# FlightControl.net
KiCad netlist of a schematic drawn in EAGLE
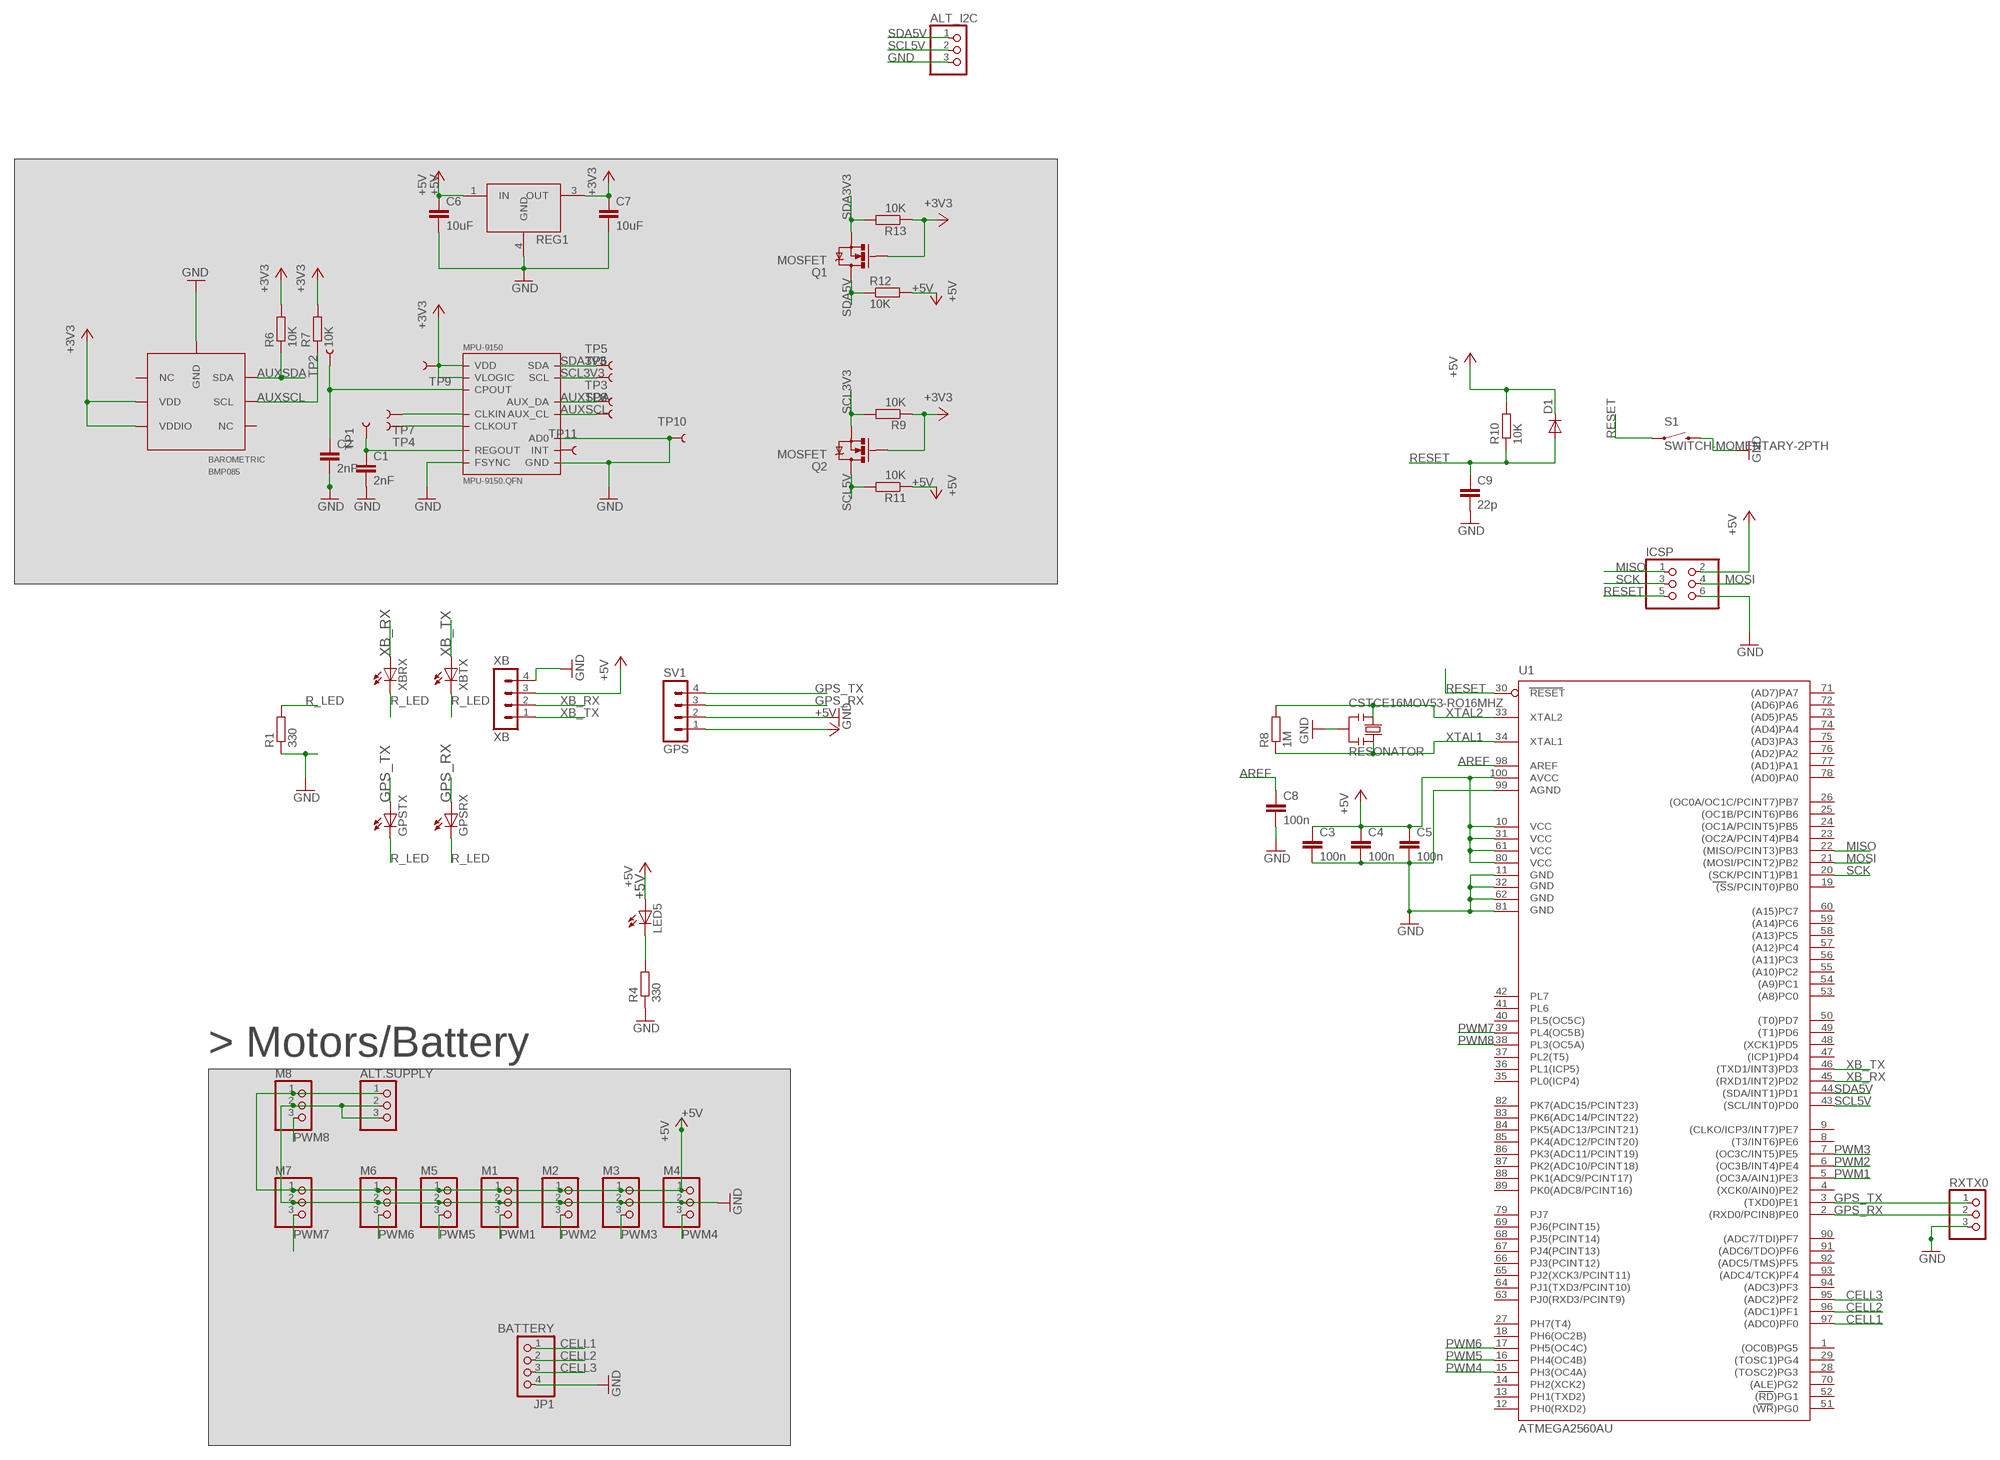
[diagram p0: schematic, sheet 1]

(export (version "E")
  (design (tool "Eeschema 10.0.6"))
  (components
    (comp (ref "ALT.SUPPLY")
      (value "PINHD-1X3")
      (footprint "eagle-import:1X03")
      (libsource (lib "eagle-import") (part "PINHD-1X3"))
    )
    (comp (ref "ALT_I2C")
      (value "PINHD-1X3")
      (footprint "eagle-import:1X03")
      (libsource (lib "eagle-import") (part "PINHD-1X3"))
    )
    (comp (ref "BAROMETRIC")
      (value "BMP085")
      (footprint "eagle-import:7LGA")
      (libsource (lib "eagle-import") (part "BMP085"))
    )
    (comp (ref "BATTERY")
      (value "JP1")
      (footprint "eagle-import:1X04")
      (libsource (lib "eagle-import") (part "PINHD-1X4"))
    )
    (comp (ref "C1")
      (value "2nF")
      (footprint "eagle-import:C0603-ROUND")
      (libsource (lib "eagle-import") (part "C-EUC0603"))
    )
    (comp (ref "C2")
      (value "2nF")
      (footprint "eagle-import:C0603-ROUND")
      (libsource (lib "eagle-import") (part "C-EUC0603"))
    )
    (comp (ref "C3")
      (value "100n")
      (footprint "eagle-import:C0603-ROUND")
      (libsource (lib "eagle-import") (part "C-EU0603-RND"))
    )
    (comp (ref "C4")
      (value "100n")
      (footprint "eagle-import:C0603-ROUND")
      (libsource (lib "eagle-import") (part "C-EU0603-RND"))
    )
    (comp (ref "C5")
      (value "100n")
      (footprint "eagle-import:C0603-ROUND")
      (libsource (lib "eagle-import") (part "C-EU0603-RND"))
    )
    (comp (ref "C6")
      (value "10uF")
      (footprint "eagle-import:CAP-PTH-SMALLEZ")
      (libsource (lib "eagle-import") (part "CAPEZ"))
    )
    (comp (ref "C7")
      (value "10uF")
      (footprint "eagle-import:CAP-PTH-SMALLEZ")
      (libsource (lib "eagle-import") (part "CAPEZ"))
    )
    (comp (ref "C8")
      (value "100n")
      (footprint "eagle-import:C0603-ROUND")
      (libsource (lib "eagle-import") (part "C-EU0603-RND"))
    )
    (comp (ref "C9")
      (value "22p")
      (footprint "eagle-import:C0603-ROUND")
      (libsource (lib "eagle-import") (part "C-EU0603-RND"))
    )
    (comp (ref "CSTCE16MOV53-RO16MHZ")
      (value "RESONATOR")
      (footprint "eagle-import:RESONATOR")
      (libsource (lib "eagle-import") (part "RESONATORMU"))
    )
    (comp (ref "D1")
      (value "DIODE-MINIMELF")
      (footprint "eagle-import:MINIMELF")
      (libsource (lib "eagle-import") (part "DIODE-MINIMELF"))
    )
    (comp (ref "GPSRX")
      (value "LEDCHIPLED_1206")
      (footprint "eagle-import:CHIPLED_1206")
      (libsource (lib "eagle-import") (part "LEDCHIPLED_1206"))
    )
    (comp (ref "GPSTX")
      (value "LEDCHIPLED_1206")
      (footprint "eagle-import:CHIPLED_1206")
      (libsource (lib "eagle-import") (part "LEDCHIPLED_1206"))
    )
    (comp (ref "ICSP")
      (value "PINHD-2X3")
      (footprint "eagle-import:2X03")
      (libsource (lib "eagle-import") (part "PINHD-2X3"))
    )
    (comp (ref "LED5")
      (value "LEDCHIPLED_1206")
      (footprint "eagle-import:CHIPLED_1206")
      (libsource (lib "eagle-import") (part "LEDCHIPLED_1206"))
    )
    (comp (ref "M1")
      (value "PINHD-1X3")
      (footprint "eagle-import:1X03")
      (libsource (lib "eagle-import") (part "PINHD-1X3"))
    )
    (comp (ref "M2")
      (value "PINHD-1X3")
      (footprint "eagle-import:1X03")
      (libsource (lib "eagle-import") (part "PINHD-1X3"))
    )
    (comp (ref "M3")
      (value "PINHD-1X3")
      (footprint "eagle-import:1X03")
      (libsource (lib "eagle-import") (part "PINHD-1X3"))
    )
    (comp (ref "M4")
      (value "PINHD-1X3")
      (footprint "eagle-import:1X03")
      (libsource (lib "eagle-import") (part "PINHD-1X3"))
    )
    (comp (ref "M5")
      (value "PINHD-1X3")
      (footprint "eagle-import:1X03")
      (libsource (lib "eagle-import") (part "PINHD-1X3"))
    )
    (comp (ref "M6")
      (value "PINHD-1X3")
      (footprint "eagle-import:1X03")
      (libsource (lib "eagle-import") (part "PINHD-1X3"))
    )
    (comp (ref "M7")
      (value "PINHD-1X3")
      (footprint "eagle-import:1X03")
      (libsource (lib "eagle-import") (part "PINHD-1X3"))
    )
    (comp (ref "M8")
      (value "PINHD-1X3")
      (footprint "eagle-import:1X03")
      (libsource (lib "eagle-import") (part "PINHD-1X3"))
    )
    (comp (ref "MPU-9150")
      (value "MPU-9150.QFN")
      (footprint "eagle-import:QFN.24.4X4")
      (libsource (lib "eagle-import") (part "MPU-9150.QFN"))
    )
    (comp (ref "Q1")
      (value "MOSFET")
      (footprint "eagle-import:SOT23")
      (libsource (lib "eagle-import") (part "MOSFET-NCHANNELBSS138"))
    )
    (comp (ref "Q2")
      (value "MOSFET")
      (footprint "eagle-import:SOT23")
      (libsource (lib "eagle-import") (part "MOSFET-NCHANNELBSS138"))
    )
    (comp (ref "R1")
      (value "330")
      (footprint "eagle-import:R0603-ROUND")
      (libsource (lib "eagle-import") (part "R-EU_0603-RND"))
    )
    (comp (ref "R4")
      (value "330")
      (footprint "eagle-import:R0603-ROUND")
      (libsource (lib "eagle-import") (part "R-EU_0603-RND"))
    )
    (comp (ref "R6")
      (value "10K")
      (footprint "eagle-import:R0603-ROUND")
      (libsource (lib "eagle-import") (part "R-EU_0603-RND"))
    )
    (comp (ref "R7")
      (value "10K")
      (footprint "eagle-import:R0603-ROUND")
      (libsource (lib "eagle-import") (part "R-EU_0603-RND"))
    )
    (comp (ref "R8")
      (value "1M")
      (footprint "eagle-import:R0603-ROUND")
      (libsource (lib "eagle-import") (part "R-EU_R0603"))
    )
    (comp (ref "R9")
      (value "10K")
      (footprint "eagle-import:R0603-ROUND")
      (libsource (lib "eagle-import") (part "R-EU_R0603"))
    )
    (comp (ref "R10")
      (value "10K")
      (footprint "eagle-import:R0603-ROUND")
      (libsource (lib "eagle-import") (part "R-EU_R0603"))
    )
    (comp (ref "R11")
      (value "10K")
      (footprint "eagle-import:R0603-ROUND")
      (libsource (lib "eagle-import") (part "R-EU_R0603"))
    )
    (comp (ref "R12")
      (value "10K")
      (footprint "eagle-import:R0603-ROUND")
      (libsource (lib "eagle-import") (part "R-EU_R0603"))
    )
    (comp (ref "R13")
      (value "10K")
      (footprint "eagle-import:R0603-ROUND")
      (libsource (lib "eagle-import") (part "R-EU_R0603"))
    )
    (comp (ref "REG1")
      (value "LD39300")
      (footprint "eagle-import:DPAK")
      (libsource (lib "eagle-import") (part "LD39300"))
    )
    (comp (ref "RXTX0")
      (value "PINHD-1X3")
      (footprint "eagle-import:1X03")
      (libsource (lib "eagle-import") (part "PINHD-1X3"))
    )
    (comp (ref "S1")
      (value "SWITCH-MOMENTARY-2PTH")
      (footprint "eagle-import:TACTILE-PTH")
      (libsource (lib "eagle-import") (part "SWITCH-MOMENTARY-2PTH"))
    )
    (comp (ref "SV1")
      (value "GPS")
      (footprint "eagle-import:MA04-1")
      (libsource (lib "eagle-import") (part "MA04-1"))
    )
    (comp (ref "TP1")
      (value "TEST-POINT3X5")
      (footprint "eagle-import:PAD.03X.05")
      (libsource (lib "eagle-import") (part "TEST-POINT3X5"))
    )
    (comp (ref "TP2")
      (value "TEST-POINT3X5")
      (footprint "eagle-import:PAD.03X.05")
      (libsource (lib "eagle-import") (part "TEST-POINT3X5"))
    )
    (comp (ref "TP3")
      (value "TEST-POINT3X5")
      (footprint "eagle-import:PAD.03X.05")
      (libsource (lib "eagle-import") (part "TEST-POINT3X5"))
    )
    (comp (ref "TP4")
      (value "TEST-POINT3X5")
      (footprint "eagle-import:PAD.03X.05")
      (libsource (lib "eagle-import") (part "TEST-POINT3X5"))
    )
    (comp (ref "TP5")
      (value "TEST-POINT3X5")
      (footprint "eagle-import:PAD.03X.05")
      (libsource (lib "eagle-import") (part "TEST-POINT3X5"))
    )
    (comp (ref "TP6")
      (value "TEST-POINT3X5")
      (footprint "eagle-import:PAD.03X.05")
      (libsource (lib "eagle-import") (part "TEST-POINT3X5"))
    )
    (comp (ref "TP7")
      (value "TEST-POINT3X5")
      (footprint "eagle-import:PAD.03X.05")
      (libsource (lib "eagle-import") (part "TEST-POINT3X5"))
    )
    (comp (ref "TP8")
      (value "TEST-POINT3X5")
      (footprint "eagle-import:PAD.03X.05")
      (libsource (lib "eagle-import") (part "TEST-POINT3X5"))
    )
    (comp (ref "TP9")
      (value "TEST-POINT3X5")
      (footprint "eagle-import:PAD.03X.05")
      (libsource (lib "eagle-import") (part "TEST-POINT3X5"))
    )
    (comp (ref "TP10")
      (value "TEST-POINT3X5")
      (footprint "eagle-import:PAD.03X.05")
      (libsource (lib "eagle-import") (part "TEST-POINT3X5"))
    )
    (comp (ref "TP11")
      (value "TEST-POINT3X5")
      (footprint "eagle-import:PAD.03X.05")
      (libsource (lib "eagle-import") (part "TEST-POINT3X5"))
    )
    (comp (ref "U1")
      (value "ATMEGA2560AU")
      (footprint "eagle-import:TQFP100")
      (libsource (lib "eagle-import") (part "ATMEGA2560AU"))
    )
    (comp (ref "XB")
      (value "XB")
      (footprint "eagle-import:MA04-1")
      (libsource (lib "eagle-import") (part "MA04-1"))
    )
    (comp (ref "XBRX")
      (value "LEDCHIPLED_1206")
      (footprint "eagle-import:CHIPLED_1206")
      (libsource (lib "eagle-import") (part "LEDCHIPLED_1206"))
    )
    (comp (ref "XBTX")
      (value "LEDCHIPLED_1206")
      (footprint "eagle-import:CHIPLED_1206")
      (libsource (lib "eagle-import") (part "LEDCHIPLED_1206"))
    )
  )
  (nets
    (net (code "1") (name "+3V3") (class "Default")
      (node (ref "BAROMETRIC") (pin "2") (pinfunction "VDD_2") (pintype "bidirectional"))
      (node (ref "BAROMETRIC") (pin "3") (pinfunction "VDDIO_3") (pintype "bidirectional"))
      (node (ref "C7") (pin "1") (pinfunction "1_1") (pintype "passive"))
      (node (ref "MPU-9150") (pin "13") (pinfunction "VDD_13") (pintype "bidirectional"))
      (node (ref "MPU-9150") (pin "3") (pinfunction "VDD_3") (pintype "bidirectional"))
      (node (ref "MPU-9150") (pin "8") (pinfunction "VLOGIC_8") (pintype "bidirectional"))
      (node (ref "Q1") (pin "1") (pinfunction "G_1") (pintype "passive"))
      (node (ref "Q2") (pin "1") (pinfunction "G_1") (pintype "passive"))
      (node (ref "R13") (pin "1") (pinfunction "1_1") (pintype "passive"))
      (node (ref "R6") (pin "2") (pinfunction "2_2") (pintype "passive"))
      (node (ref "R7") (pin "2") (pinfunction "2_2") (pintype "passive"))
      (node (ref "R9") (pin "1") (pinfunction "1_1") (pintype "passive"))
      (node (ref "REG1") (pin "3") (pinfunction "OUT_3") (pintype "bidirectional"))
      (node (ref "TP9") (pin "P$1") (pinfunction "1_P$1") (pintype "bidirectional"))
    )
    (net (code "2") (name "+5V") (class "Default")
      (node (ref "ALT.SUPPLY") (pin "1") (pinfunction "1_1") (pintype "passive"))
      (node (ref "C3") (pin "1") (pinfunction "1_1") (pintype "passive"))
      (node (ref "C4") (pin "1") (pinfunction "1_1") (pintype "passive"))
      (node (ref "C5") (pin "1") (pinfunction "1_1") (pintype "passive"))
      (node (ref "C6") (pin "1") (pinfunction "1_1") (pintype "passive"))
      (node (ref "D1") (pin "C") (pinfunction "C_C") (pintype "passive"))
      (node (ref "ICSP") (pin "2") (pinfunction "2_2") (pintype "passive"))
      (node (ref "LED5") (pin "A") (pinfunction "A_A") (pintype "passive"))
      (node (ref "M1") (pin "1") (pinfunction "1_1") (pintype "passive"))
      (node (ref "M2") (pin "1") (pinfunction "1_1") (pintype "passive"))
      (node (ref "M3") (pin "1") (pinfunction "1_1") (pintype "passive"))
      (node (ref "M4") (pin "1") (pinfunction "1_1") (pintype "passive"))
      (node (ref "M5") (pin "1") (pinfunction "1_1") (pintype "passive"))
      (node (ref "M6") (pin "1") (pinfunction "1_1") (pintype "passive"))
      (node (ref "M7") (pin "1") (pinfunction "1_1") (pintype "passive"))
      (node (ref "M8") (pin "1") (pinfunction "1_1") (pintype "passive"))
      (node (ref "R10") (pin "2") (pinfunction "2_2") (pintype "passive"))
      (node (ref "R11") (pin "1") (pinfunction "1_1") (pintype "passive"))
      (node (ref "R12") (pin "2") (pinfunction "2_2") (pintype "passive"))
      (node (ref "REG1") (pin "1") (pinfunction "IN_1") (pintype "bidirectional"))
      (node (ref "SV1") (pin "1") (pinfunction "1_1") (pintype "passive"))
      (node (ref "U1") (pin "10") (pinfunction "VCC_10") (pintype "power_in"))
      (node (ref "U1") (pin "100") (pinfunction "AVCC_100") (pintype "power_in"))
      (node (ref "U1") (pin "31") (pinfunction "VCC1_31") (pintype "power_in"))
      (node (ref "U1") (pin "61") (pinfunction "VCC2_61") (pintype "power_in"))
      (node (ref "U1") (pin "80") (pinfunction "VCC3_80") (pintype "power_in"))
      (node (ref "XB") (pin "3") (pinfunction "3_3") (pintype "passive"))
    )
    (net (code "3") (name "/AREF") (class "Default")
      (node (ref "C8") (pin "1") (pinfunction "1_1") (pintype "passive"))
      (node (ref "U1") (pin "98") (pinfunction "AREF_98") (pintype "bidirectional"))
    )
    (net (code "4") (name "/AUXSCL") (class "Default")
      (node (ref "BAROMETRIC") (pin "5") (pinfunction "SCL_5") (pintype "bidirectional"))
      (node (ref "MPU-9150") (pin "7") (pinfunction "AUX_CL_7") (pintype "bidirectional"))
      (node (ref "R7") (pin "1") (pinfunction "1_1") (pintype "passive"))
      (node (ref "TP8") (pin "P$1") (pinfunction "1_P$1") (pintype "bidirectional"))
    )
    (net (code "5") (name "/AUXSDA") (class "Default")
      (node (ref "BAROMETRIC") (pin "6") (pinfunction "SDA_6") (pintype "bidirectional"))
      (node (ref "MPU-9150") (pin "6") (pinfunction "AUX_DA_6") (pintype "bidirectional"))
      (node (ref "R6") (pin "1") (pinfunction "1_1") (pintype "passive"))
      (node (ref "TP3") (pin "P$1") (pinfunction "1_P$1") (pintype "bidirectional"))
    )
    (net (code "6") (name "/CELL1") (class "Default")
      (node (ref "BATTERY") (pin "1") (pinfunction "1_1") (pintype "passive"))
      (node (ref "U1") (pin "97") (pinfunction "(ADC0)PF0_97") (pintype "bidirectional"))
    )
    (net (code "7") (name "/CELL2") (class "Default")
      (node (ref "BATTERY") (pin "2") (pinfunction "2_2") (pintype "passive"))
      (node (ref "U1") (pin "96") (pinfunction "(ADC1)PF1_96") (pintype "bidirectional"))
    )
    (net (code "8") (name "/CELL3") (class "Default")
      (node (ref "BATTERY") (pin "3") (pinfunction "3_3") (pintype "passive"))
      (node (ref "U1") (pin "95") (pinfunction "(ADC2)PF2_95") (pintype "bidirectional"))
    )
    (net (code "9") (name "/GPS_RX") (class "Default")
      (node (ref "GPSRX") (pin "A") (pinfunction "A_A") (pintype "passive"))
      (node (ref "RXTX0") (pin "2") (pinfunction "2_2") (pintype "passive"))
      (node (ref "SV1") (pin "3") (pinfunction "3_3") (pintype "passive"))
      (node (ref "U1") (pin "2") (pinfunction "(RXD0/PCIN8)PE0_2") (pintype "bidirectional"))
    )
    (net (code "10") (name "/GPS_TX") (class "Default")
      (node (ref "GPSTX") (pin "A") (pinfunction "A_A") (pintype "passive"))
      (node (ref "RXTX0") (pin "1") (pinfunction "1_1") (pintype "passive"))
      (node (ref "SV1") (pin "4") (pinfunction "4_4") (pintype "passive"))
      (node (ref "U1") (pin "3") (pinfunction "(TXD0)PE1_3") (pintype "bidirectional"))
    )
    (net (code "11") (name "/MISO") (class "Default")
      (node (ref "ICSP") (pin "1") (pinfunction "1_1") (pintype "passive"))
      (node (ref "U1") (pin "22") (pinfunction "(MISO/PCINT3)PB3_22") (pintype "bidirectional"))
    )
    (net (code "12") (name "/MOSI") (class "Default")
      (node (ref "ICSP") (pin "4") (pinfunction "4_4") (pintype "passive"))
      (node (ref "U1") (pin "21") (pinfunction "(MOSI/PCINT2)PB2_21") (pintype "bidirectional"))
    )
    (net (code "13") (name "/PWM1") (class "Default")
      (node (ref "M1") (pin "3") (pinfunction "3_3") (pintype "passive"))
      (node (ref "U1") (pin "5") (pinfunction "(OC3A/AIN1)PE3_5") (pintype "bidirectional"))
    )
    (net (code "14") (name "/PWM2") (class "Default")
      (node (ref "M2") (pin "3") (pinfunction "3_3") (pintype "passive"))
      (node (ref "U1") (pin "6") (pinfunction "(OC3B/INT4)PE4_6") (pintype "bidirectional"))
    )
    (net (code "15") (name "/PWM3") (class "Default")
      (node (ref "M3") (pin "3") (pinfunction "3_3") (pintype "passive"))
      (node (ref "U1") (pin "7") (pinfunction "(OC3C/INT5)PE5_7") (pintype "bidirectional"))
    )
    (net (code "16") (name "/PWM4") (class "Default")
      (node (ref "M4") (pin "3") (pinfunction "3_3") (pintype "passive"))
      (node (ref "U1") (pin "15") (pinfunction "PH3(OC4A)_15") (pintype "bidirectional"))
    )
    (net (code "17") (name "/PWM5") (class "Default")
      (node (ref "M5") (pin "3") (pinfunction "3_3") (pintype "passive"))
      (node (ref "U1") (pin "16") (pinfunction "PH4(OC4B)_16") (pintype "bidirectional"))
    )
    (net (code "18") (name "/PWM6") (class "Default")
      (node (ref "M6") (pin "3") (pinfunction "3_3") (pintype "passive"))
      (node (ref "U1") (pin "17") (pinfunction "PH5(OC4C)_17") (pintype "bidirectional"))
    )
    (net (code "19") (name "/PWM7") (class "Default")
      (node (ref "M7") (pin "3") (pinfunction "3_3") (pintype "passive"))
      (node (ref "U1") (pin "39") (pinfunction "PL4(OC5B)_39") (pintype "bidirectional"))
    )
    (net (code "20") (name "/PWM8") (class "Default")
      (node (ref "M8") (pin "3") (pinfunction "3_3") (pintype "passive"))
      (node (ref "U1") (pin "38") (pinfunction "PL3(OC5A)_38") (pintype "bidirectional"))
    )
    (net (code "21") (name "/RESET") (class "Default")
      (node (ref "C9") (pin "1") (pinfunction "1_1") (pintype "passive"))
      (node (ref "D1") (pin "A") (pinfunction "A_A") (pintype "passive"))
      (node (ref "ICSP") (pin "5") (pinfunction "5_5") (pintype "passive"))
      (node (ref "R10") (pin "1") (pinfunction "1_1") (pintype "passive"))
      (node (ref "S1") (pin "1") (pinfunction "1_1") (pintype "passive"))
      (node (ref "U1") (pin "30") (pinfunction "RESET_30") (pintype "input"))
    )
    (net (code "22") (name "/R_LED") (class "Default")
      (node (ref "GPSRX") (pin "C") (pinfunction "C_C") (pintype "passive"))
      (node (ref "GPSTX") (pin "C") (pinfunction "C_C") (pintype "passive"))
      (node (ref "R1") (pin "2") (pinfunction "2_2") (pintype "passive"))
      (node (ref "XBRX") (pin "C") (pinfunction "C_C") (pintype "passive"))
      (node (ref "XBTX") (pin "C") (pinfunction "C_C") (pintype "passive"))
    )
    (net (code "23") (name "/SCK") (class "Default")
      (node (ref "ICSP") (pin "3") (pinfunction "3_3") (pintype "passive"))
      (node (ref "U1") (pin "20") (pinfunction "(SCK/PCINT1)PB1_20") (pintype "bidirectional"))
    )
    (net (code "24") (name "/SCL3V3") (class "Default")
      (node (ref "MPU-9150") (pin "23") (pinfunction "SCL_23") (pintype "bidirectional"))
      (node (ref "Q2") (pin "2") (pinfunction "S_2") (pintype "passive"))
      (node (ref "R9") (pin "2") (pinfunction "2_2") (pintype "passive"))
      (node (ref "TP6") (pin "P$1") (pinfunction "1_P$1") (pintype "bidirectional"))
    )
    (net (code "25") (name "/SCL5V") (class "Default")
      (node (ref "ALT_I2C") (pin "2") (pinfunction "2_2") (pintype "passive"))
      (node (ref "Q2") (pin "3") (pinfunction "D_3") (pintype "passive"))
      (node (ref "R11") (pin "2") (pinfunction "2_2") (pintype "passive"))
      (node (ref "U1") (pin "43") (pinfunction "(SCL/INT0)PD0_43") (pintype "bidirectional"))
    )
    (net (code "26") (name "/SDA3V3") (class "Default")
      (node (ref "MPU-9150") (pin "24") (pinfunction "SDA_24") (pintype "bidirectional"))
      (node (ref "Q1") (pin "2") (pinfunction "S_2") (pintype "passive"))
      (node (ref "R13") (pin "2") (pinfunction "2_2") (pintype "passive"))
      (node (ref "TP5") (pin "P$1") (pinfunction "1_P$1") (pintype "bidirectional"))
    )
    (net (code "27") (name "/SDA5V") (class "Default")
      (node (ref "ALT_I2C") (pin "1") (pinfunction "1_1") (pintype "passive"))
      (node (ref "Q1") (pin "3") (pinfunction "D_3") (pintype "passive"))
      (node (ref "R12") (pin "1") (pinfunction "1_1") (pintype "passive"))
      (node (ref "U1") (pin "44") (pinfunction "(SDA/INT1)PD1_44") (pintype "bidirectional"))
    )
    (net (code "28") (name "/XB_RX") (class "Default")
      (node (ref "U1") (pin "45") (pinfunction "(RXD1/INT2)PD2_45") (pintype "bidirectional"))
      (node (ref "XB") (pin "2") (pinfunction "2_2") (pintype "passive"))
      (node (ref "XBRX") (pin "A") (pinfunction "A_A") (pintype "passive"))
    )
    (net (code "29") (name "/XB_TX") (class "Default")
      (node (ref "U1") (pin "46") (pinfunction "(TXD1/INT3)PD3_46") (pintype "bidirectional"))
      (node (ref "XB") (pin "1") (pinfunction "1_1") (pintype "passive"))
      (node (ref "XBTX") (pin "A") (pinfunction "A_A") (pintype "passive"))
    )
    (net (code "30") (name "/XTAL1") (class "Default")
      (node (ref "CSTCE16MOV53-RO16MHZ") (pin "3") (pinfunction "3_3") (pintype "passive"))
      (node (ref "R8") (pin "1") (pinfunction "1_1") (pintype "passive"))
      (node (ref "U1") (pin "34") (pinfunction "XTAL1_34") (pintype "input"))
    )
    (net (code "31") (name "/XTAL2") (class "Default")
      (node (ref "CSTCE16MOV53-RO16MHZ") (pin "1") (pinfunction "1_1") (pintype "passive"))
      (node (ref "R8") (pin "2") (pinfunction "2_2") (pintype "passive"))
      (node (ref "U1") (pin "33") (pinfunction "XTAL2_33") (pintype "output"))
    )
    (net (code "32") (name "GND") (class "Default")
      (node (ref "ALT.SUPPLY") (pin "2") (pinfunction "2_2") (pintype "passive"))
      (node (ref "ALT.SUPPLY") (pin "3") (pinfunction "3_3") (pintype "passive"))
      (node (ref "ALT_I2C") (pin "3") (pinfunction "3_3") (pintype "passive"))
      (node (ref "BAROMETRIC") (pin "7") (pinfunction "GND_7") (pintype "bidirectional"))
      (node (ref "BATTERY") (pin "4") (pinfunction "4_4") (pintype "passive"))
      (node (ref "C1") (pin "2") (pinfunction "2_2") (pintype "passive"))
      (node (ref "C2") (pin "2") (pinfunction "2_2") (pintype "passive"))
      (node (ref "C3") (pin "2") (pinfunction "2_2") (pintype "passive"))
      (node (ref "C4") (pin "2") (pinfunction "2_2") (pintype "passive"))
      (node (ref "C5") (pin "2") (pinfunction "2_2") (pintype "passive"))
      (node (ref "C6") (pin "2") (pinfunction "2_2") (pintype "passive"))
      (node (ref "C7") (pin "2") (pinfunction "2_2") (pintype "passive"))
      (node (ref "C8") (pin "2") (pinfunction "2_2") (pintype "passive"))
      (node (ref "C9") (pin "2") (pinfunction "2_2") (pintype "passive"))
      (node (ref "CSTCE16MOV53-RO16MHZ") (pin "2") (pinfunction "2_2") (pintype "passive"))
      (node (ref "ICSP") (pin "6") (pinfunction "6_6") (pintype "passive"))
      (node (ref "M1") (pin "2") (pinfunction "2_2") (pintype "passive"))
      (node (ref "M2") (pin "2") (pinfunction "2_2") (pintype "passive"))
      (node (ref "M3") (pin "2") (pinfunction "2_2") (pintype "passive"))
      (node (ref "M4") (pin "2") (pinfunction "2_2") (pintype "passive"))
      (node (ref "M5") (pin "2") (pinfunction "2_2") (pintype "passive"))
      (node (ref "M6") (pin "2") (pinfunction "2_2") (pintype "passive"))
      (node (ref "M7") (pin "2") (pinfunction "2_2") (pintype "passive"))
      (node (ref "M8") (pin "2") (pinfunction "2_2") (pintype "passive"))
      (node (ref "MPU-9150") (pin "11") (pinfunction "FSYNC_11") (pintype "bidirectional"))
      (node (ref "MPU-9150") (pin "15") (pinfunction "GND_15") (pintype "bidirectional"))
      (node (ref "MPU-9150") (pin "17") (pinfunction "GND_17") (pintype "bidirectional"))
      (node (ref "MPU-9150") (pin "18") (pinfunction "GND_18") (pintype "bidirectional"))
      (node (ref "MPU-9150") (pin "9") (pinfunction "AD0_9") (pintype "bidirectional"))
      (node (ref "R1") (pin "1") (pinfunction "1_1") (pintype "passive"))
      (node (ref "R4") (pin "1") (pinfunction "1_1") (pintype "passive"))
      (node (ref "REG1") (pin "4") (pinfunction "GND_4") (pintype "bidirectional"))
      (node (ref "RXTX0") (pin "3") (pinfunction "3_3") (pintype "passive"))
      (node (ref "S1") (pin "3") (pinfunction "2_3") (pintype "passive"))
      (node (ref "SV1") (pin "2") (pinfunction "2_2") (pintype "passive"))
      (node (ref "TP10") (pin "P$1") (pinfunction "1_P$1") (pintype "bidirectional"))
      (node (ref "U1") (pin "11") (pinfunction "GND_11") (pintype "power_in"))
      (node (ref "U1") (pin "32") (pinfunction "GND1_32") (pintype "power_in"))
      (node (ref "U1") (pin "62") (pinfunction "GND2_62") (pintype "power_in"))
      (node (ref "U1") (pin "81") (pinfunction "GND3_81") (pintype "power_in"))
      (node (ref "U1") (pin "99") (pinfunction "AGND_99") (pintype "power_in"))
      (node (ref "XB") (pin "4") (pinfunction "4_4") (pintype "passive"))
    )
    (net (code "33") (name "Net-(LED5-PadC)") (class "Default")
      (node (ref "LED5") (pin "C") (pinfunction "C_C") (pintype "passive"))
      (node (ref "R4") (pin "2") (pinfunction "2_2") (pintype "passive"))
    )
    (net (code "34") (name "Net-(MPU-9150-CLKIN)") (class "Default")
      (node (ref "MPU-9150") (pin "1") (pinfunction "CLKIN_1") (pintype "bidirectional"))
      (node (ref "TP7") (pin "P$1") (pinfunction "1_P$1") (pintype "bidirectional"))
    )
    (net (code "35") (name "Net-(MPU-9150-CLKOUT)") (class "Default")
      (node (ref "MPU-9150") (pin "22") (pinfunction "CLKOUT_22") (pintype "bidirectional"))
      (node (ref "TP4") (pin "P$1") (pinfunction "1_P$1") (pintype "bidirectional"))
    )
    (net (code "36") (name "Net-(MPU-9150-CPOUT)") (class "Default")
      (node (ref "C2") (pin "1") (pinfunction "1_1") (pintype "passive"))
      (node (ref "MPU-9150") (pin "20") (pinfunction "CPOUT_20") (pintype "bidirectional"))
      (node (ref "TP2") (pin "P$1") (pinfunction "1_P$1") (pintype "bidirectional"))
    )
    (net (code "37") (name "Net-(MPU-9150-INT)") (class "Default")
      (node (ref "MPU-9150") (pin "12") (pinfunction "INT_12") (pintype "bidirectional"))
      (node (ref "TP11") (pin "P$1") (pinfunction "1_P$1") (pintype "bidirectional"))
    )
    (net (code "38") (name "Net-(MPU-9150-REGOUT)") (class "Default")
      (node (ref "C1") (pin "1") (pinfunction "1_1") (pintype "passive"))
      (node (ref "MPU-9150") (pin "10") (pinfunction "REGOUT_10") (pintype "bidirectional"))
      (node (ref "TP1") (pin "P$1") (pinfunction "1_P$1") (pintype "bidirectional"))
    )
    (net (code "39") (name "unconnected-(BAROMETRIC-NC-Pad1)") (class "Default")
      (node (ref "BAROMETRIC") (pin "1") (pinfunction "NC_1") (pintype "bidirectional"))
    )
    (net (code "40") (name "unconnected-(BAROMETRIC-NC-Pad4)") (class "Default")
      (node (ref "BAROMETRIC") (pin "4") (pinfunction "NC_4") (pintype "bidirectional"))
    )
    (net (code "41") (name "unconnected-(U1-(A8)PC0-Pad53)") (class "Default")
      (node (ref "U1") (pin "53") (pinfunction "(A8)PC0_53") (pintype "bidirectional"))
    )
    (net (code "42") (name "unconnected-(U1-(A9)PC1-Pad54)") (class "Default")
      (node (ref "U1") (pin "54") (pinfunction "(A9)PC1_54") (pintype "bidirectional"))
    )
    (net (code "43") (name "unconnected-(U1-(A10)PC2-Pad55)") (class "Default")
      (node (ref "U1") (pin "55") (pinfunction "(A10)PC2_55") (pintype "bidirectional"))
    )
    (net (code "44") (name "unconnected-(U1-(A11)PC3-Pad56)") (class "Default")
      (node (ref "U1") (pin "56") (pinfunction "(A11)PC3_56") (pintype "bidirectional"))
    )
    (net (code "45") (name "unconnected-(U1-(A12)PC4-Pad57)") (class "Default")
      (node (ref "U1") (pin "57") (pinfunction "(A12)PC4_57") (pintype "bidirectional"))
    )
    (net (code "46") (name "unconnected-(U1-(A13)PC5-Pad58)") (class "Default")
      (node (ref "U1") (pin "58") (pinfunction "(A13)PC5_58") (pintype "bidirectional"))
    )
    (net (code "47") (name "unconnected-(U1-(A14)PC6-Pad59)") (class "Default")
      (node (ref "U1") (pin "59") (pinfunction "(A14)PC6_59") (pintype "bidirectional"))
    )
    (net (code "48") (name "unconnected-(U1-(A15)PC7-Pad60)") (class "Default")
      (node (ref "U1") (pin "60") (pinfunction "(A15)PC7_60") (pintype "bidirectional"))
    )
    (net (code "49") (name "unconnected-(U1-(AD0)PA0-Pad78)") (class "Default")
      (node (ref "U1") (pin "78") (pinfunction "(AD0)PA0_78") (pintype "bidirectional"))
    )
    (net (code "50") (name "unconnected-(U1-(AD1)PA1-Pad77)") (class "Default")
      (node (ref "U1") (pin "77") (pinfunction "(AD1)PA1_77") (pintype "bidirectional"))
    )
    (net (code "51") (name "unconnected-(U1-(AD2)PA2-Pad76)") (class "Default")
      (node (ref "U1") (pin "76") (pinfunction "(AD2)PA2_76") (pintype "bidirectional"))
    )
    (net (code "52") (name "unconnected-(U1-(AD3)PA3-Pad75)") (class "Default")
      (node (ref "U1") (pin "75") (pinfunction "(AD3)PA3_75") (pintype "bidirectional"))
    )
    (net (code "53") (name "unconnected-(U1-(AD4)PA4-Pad74)") (class "Default")
      (node (ref "U1") (pin "74") (pinfunction "(AD4)PA4_74") (pintype "bidirectional"))
    )
    (net (code "54") (name "unconnected-(U1-(AD5)PA5-Pad73)") (class "Default")
      (node (ref "U1") (pin "73") (pinfunction "(AD5)PA5_73") (pintype "bidirectional"))
    )
    (net (code "55") (name "unconnected-(U1-(AD6)PA6-Pad72)") (class "Default")
      (node (ref "U1") (pin "72") (pinfunction "(AD6)PA6_72") (pintype "bidirectional"))
    )
    (net (code "56") (name "unconnected-(U1-(AD7)PA7-Pad71)") (class "Default")
      (node (ref "U1") (pin "71") (pinfunction "(AD7)PA7_71") (pintype "bidirectional"))
    )
    (net (code "57") (name "unconnected-(U1-(ADC3)PF3-Pad94)") (class "Default")
      (node (ref "U1") (pin "94") (pinfunction "(ADC3)PF3_94") (pintype "bidirectional"))
    )
    (net (code "58") (name "unconnected-(U1-(ADC4{slash}TCK)PF4-Pad93)") (class "Default")
      (node (ref "U1") (pin "93") (pinfunction "(ADC4/TCK)PF4_93") (pintype "bidirectional"))
    )
    (net (code "59") (name "unconnected-(U1-(ADC5{slash}TMS)PF5-Pad92)") (class "Default")
      (node (ref "U1") (pin "92") (pinfunction "(ADC5/TMS)PF5_92") (pintype "bidirectional"))
    )
    (net (code "60") (name "unconnected-(U1-(ADC6{slash}TDO)PF6-Pad91)") (class "Default")
      (node (ref "U1") (pin "91") (pinfunction "(ADC6/TDO)PF6_91") (pintype "bidirectional"))
    )
    (net (code "61") (name "unconnected-(U1-(ADC7{slash}TDI)PF7-Pad90)") (class "Default")
      (node (ref "U1") (pin "90") (pinfunction "(ADC7/TDI)PF7_90") (pintype "bidirectional"))
    )
    (net (code "62") (name "unconnected-(U1-(ALE)PG2-Pad70)") (class "Default")
      (node (ref "U1") (pin "70") (pinfunction "(ALE)PG2_70") (pintype "bidirectional"))
    )
    (net (code "63") (name "unconnected-(U1-(CLKO{slash}ICP3{slash}INT7)PE7-Pad9)") (class "Default")
      (node (ref "U1") (pin "9") (pinfunction "(CLKO/ICP3/INT7)PE7_9") (pintype "bidirectional"))
    )
    (net (code "64") (name "unconnected-(U1-(ICP1)PD4-Pad47)") (class "Default")
      (node (ref "U1") (pin "47") (pinfunction "(ICP1)PD4_47") (pintype "bidirectional"))
    )
    (net (code "65") (name "unconnected-(U1-(OC0A{slash}OC1C{slash}PCINT7)PB7-Pad26)") (class "Default")
      (node (ref "U1") (pin "26") (pinfunction "(OC0A/OC1C/PCINT7)PB7_26") (pintype "bidirectional"))
    )
    (net (code "66") (name "unconnected-(U1-(OC0B)PG5-Pad1)") (class "Default")
      (node (ref "U1") (pin "1") (pinfunction "(OC0B)PG5_1") (pintype "bidirectional"))
    )
    (net (code "67") (name "unconnected-(U1-(OC1A{slash}PCINT5)PB5-Pad24)") (class "Default")
      (node (ref "U1") (pin "24") (pinfunction "(OC1A/PCINT5)PB5_24") (pintype "bidirectional"))
    )
    (net (code "68") (name "unconnected-(U1-(OC1B{slash}PCINT6)PB6-Pad25)") (class "Default")
      (node (ref "U1") (pin "25") (pinfunction "(OC1B/PCINT6)PB6_25") (pintype "bidirectional"))
    )
    (net (code "69") (name "unconnected-(U1-(OC2A{slash}PCINT4)PB4-Pad23)") (class "Default")
      (node (ref "U1") (pin "23") (pinfunction "(OC2A/PCINT4)PB4_23") (pintype "bidirectional"))
    )
    (net (code "70") (name "unconnected-(U1-(RD)PG1-Pad52)") (class "Default")
      (node (ref "U1") (pin "52") (pinfunction "(RD)PG1_52") (pintype "bidirectional"))
    )
    (net (code "71") (name "unconnected-(U1-(SS{slash}PCINT0)PB0-Pad19)") (class "Default")
      (node (ref "U1") (pin "19") (pinfunction "(SS/PCINT0)PB0_19") (pintype "bidirectional"))
    )
    (net (code "72") (name "unconnected-(U1-(T0)PD7-Pad50)") (class "Default")
      (node (ref "U1") (pin "50") (pinfunction "(T0)PD7_50") (pintype "bidirectional"))
    )
    (net (code "73") (name "unconnected-(U1-(T1)PD6-Pad49)") (class "Default")
      (node (ref "U1") (pin "49") (pinfunction "(T1)PD6_49") (pintype "bidirectional"))
    )
    (net (code "74") (name "unconnected-(U1-(T3{slash}INT6)PE6-Pad8)") (class "Default")
      (node (ref "U1") (pin "8") (pinfunction "(T3/INT6)PE6_8") (pintype "bidirectional"))
    )
    (net (code "75") (name "unconnected-(U1-(TOSC1)PG4-Pad29)") (class "Default")
      (node (ref "U1") (pin "29") (pinfunction "(TOSC1)PG4_29") (pintype "bidirectional"))
    )
    (net (code "76") (name "unconnected-(U1-(TOSC2)PG3-Pad28)") (class "Default")
      (node (ref "U1") (pin "28") (pinfunction "(TOSC2)PG3_28") (pintype "bidirectional"))
    )
    (net (code "77") (name "unconnected-(U1-(WR)PG0-Pad51)") (class "Default")
      (node (ref "U1") (pin "51") (pinfunction "(WR)PG0_51") (pintype "bidirectional"))
    )
    (net (code "78") (name "unconnected-(U1-(XCK0{slash}AIN0)PE2-Pad4)") (class "Default")
      (node (ref "U1") (pin "4") (pinfunction "(XCK0/AIN0)PE2_4") (pintype "bidirectional"))
    )
    (net (code "79") (name "unconnected-(U1-(XCK1)PD5-Pad48)") (class "Default")
      (node (ref "U1") (pin "48") (pinfunction "(XCK1)PD5_48") (pintype "bidirectional"))
    )
    (net (code "80") (name "unconnected-(U1-PH0(RXD2)-Pad12)") (class "Default")
      (node (ref "U1") (pin "12") (pinfunction "PH0(RXD2)_12") (pintype "bidirectional"))
    )
    (net (code "81") (name "unconnected-(U1-PH1(TXD2)-Pad13)") (class "Default")
      (node (ref "U1") (pin "13") (pinfunction "PH1(TXD2)_13") (pintype "bidirectional"))
    )
    (net (code "82") (name "unconnected-(U1-PH2(XCK2)-Pad14)") (class "Default")
      (node (ref "U1") (pin "14") (pinfunction "PH2(XCK2)_14") (pintype "bidirectional"))
    )
    (net (code "83") (name "unconnected-(U1-PH6(OC2B)-Pad18)") (class "Default")
      (node (ref "U1") (pin "18") (pinfunction "PH6(OC2B)_18") (pintype "bidirectional"))
    )
    (net (code "84") (name "unconnected-(U1-PH7(T4)-Pad27)") (class "Default")
      (node (ref "U1") (pin "27") (pinfunction "PH7(T4)_27") (pintype "bidirectional"))
    )
    (net (code "85") (name "unconnected-(U1-PJ0(RXD3{slash}PCINT9)-Pad63)") (class "Default")
      (node (ref "U1") (pin "63") (pinfunction "PJ0(RXD3/PCINT9)_63") (pintype "bidirectional"))
    )
    (net (code "86") (name "unconnected-(U1-PJ1(TXD3{slash}PCINT10)-Pad64)") (class "Default")
      (node (ref "U1") (pin "64") (pinfunction "PJ1(TXD3/PCINT10)_64") (pintype "bidirectional"))
    )
    (net (code "87") (name "unconnected-(U1-PJ2(XCK3{slash}PCINT11)-Pad65)") (class "Default")
      (node (ref "U1") (pin "65") (pinfunction "PJ2(XCK3/PCINT11)_65") (pintype "bidirectional"))
    )
    (net (code "88") (name "unconnected-(U1-PJ3(PCINT12)-Pad66)") (class "Default")
      (node (ref "U1") (pin "66") (pinfunction "PJ3(PCINT12)_66") (pintype "bidirectional"))
    )
    (net (code "89") (name "unconnected-(U1-PJ4(PCINT13)-Pad67)") (class "Default")
      (node (ref "U1") (pin "67") (pinfunction "PJ4(PCINT13)_67") (pintype "bidirectional"))
    )
    (net (code "90") (name "unconnected-(U1-PJ5(PCINT14)-Pad68)") (class "Default")
      (node (ref "U1") (pin "68") (pinfunction "PJ5(PCINT14)_68") (pintype "bidirectional"))
    )
    (net (code "91") (name "unconnected-(U1-PJ6(PCINT15)-Pad69)") (class "Default")
      (node (ref "U1") (pin "69") (pinfunction "PJ6(PCINT15)_69") (pintype "bidirectional"))
    )
    (net (code "92") (name "unconnected-(U1-PJ7-Pad79)") (class "Default")
      (node (ref "U1") (pin "79") (pinfunction "PJ7_79") (pintype "bidirectional"))
    )
    (net (code "93") (name "unconnected-(U1-PK0(ADC8{slash}PCINT16)-Pad89)") (class "Default")
      (node (ref "U1") (pin "89") (pinfunction "PK0(ADC8/PCINT16)_89") (pintype "bidirectional"))
    )
    (net (code "94") (name "unconnected-(U1-PK1(ADC9{slash}PCINT17)-Pad88)") (class "Default")
      (node (ref "U1") (pin "88") (pinfunction "PK1(ADC9/PCINT17)_88") (pintype "bidirectional"))
    )
    (net (code "95") (name "unconnected-(U1-PK2(ADC10{slash}PCINT18)-Pad87)") (class "Default")
      (node (ref "U1") (pin "87") (pinfunction "PK2(ADC10/PCINT18)_87") (pintype "bidirectional"))
    )
    (net (code "96") (name "unconnected-(U1-PK3(ADC11{slash}PCINT19)-Pad86)") (class "Default")
      (node (ref "U1") (pin "86") (pinfunction "PK3(ADC11/PCINT19)_86") (pintype "bidirectional"))
    )
    (net (code "97") (name "unconnected-(U1-PK4(ADC12{slash}PCINT20)-Pad85)") (class "Default")
      (node (ref "U1") (pin "85") (pinfunction "PK4(ADC12/PCINT20)_85") (pintype "bidirectional"))
    )
    (net (code "98") (name "unconnected-(U1-PK5(ADC13{slash}PCINT21)-Pad84)") (class "Default")
      (node (ref "U1") (pin "84") (pinfunction "PK5(ADC13/PCINT21)_84") (pintype "bidirectional"))
    )
    (net (code "99") (name "unconnected-(U1-PK6(ADC14{slash}PCINT22)-Pad83)") (class "Default")
      (node (ref "U1") (pin "83") (pinfunction "PK6(ADC14/PCINT22)_83") (pintype "bidirectional"))
    )
    (net (code "100") (name "unconnected-(U1-PK7(ADC15{slash}PCINT23)-Pad82)") (class "Default")
      (node (ref "U1") (pin "82") (pinfunction "PK7(ADC15/PCINT23)_82") (pintype "bidirectional"))
    )
    (net (code "101") (name "unconnected-(U1-PL0(ICP4)-Pad35)") (class "Default")
      (node (ref "U1") (pin "35") (pinfunction "PL0(ICP4)_35") (pintype "bidirectional"))
    )
    (net (code "102") (name "unconnected-(U1-PL1(ICP5)-Pad36)") (class "Default")
      (node (ref "U1") (pin "36") (pinfunction "PL1(ICP5)_36") (pintype "bidirectional"))
    )
    (net (code "103") (name "unconnected-(U1-PL2(T5)-Pad37)") (class "Default")
      (node (ref "U1") (pin "37") (pinfunction "PL2(T5)_37") (pintype "bidirectional"))
    )
    (net (code "104") (name "unconnected-(U1-PL5(OC5C)-Pad40)") (class "Default")
      (node (ref "U1") (pin "40") (pinfunction "PL5(OC5C)_40") (pintype "bidirectional"))
    )
    (net (code "105") (name "unconnected-(U1-PL6-Pad41)") (class "Default")
      (node (ref "U1") (pin "41") (pinfunction "PL6_41") (pintype "bidirectional"))
    )
    (net (code "106") (name "unconnected-(U1-PL7-Pad42)") (class "Default")
      (node (ref "U1") (pin "42") (pinfunction "PL7_42") (pintype "bidirectional"))
    )
  )
)
